# SCH-Unified_Sheet_1_Altium.net
KiCad netlist of a schematic drawn in Altium Designer
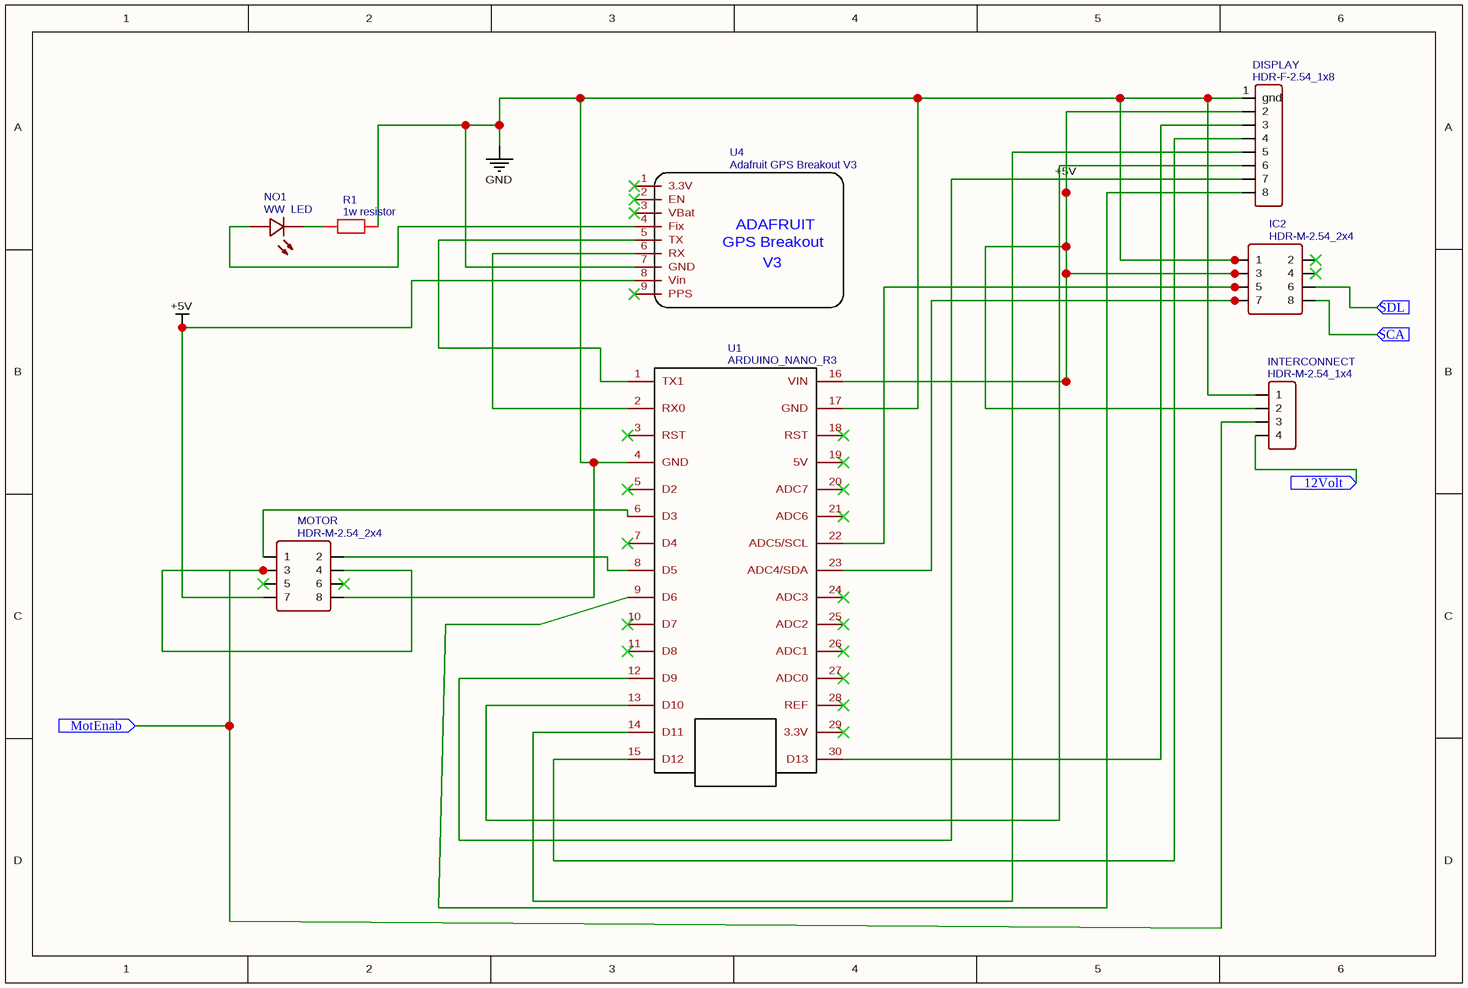
[diagram p0: SCH-Unified_Sheet_1_Altium.schdoc]

(export (version "E")
  (design (tool "Eeschema 10.0.6"))
  (components
    (comp (ref "DISPLAY")
      (value "HDR-F-2.54_1x8")
      (fields (field (name "CONTRIBUTOR") "LCEDA_Lib"))
      (libsource (lib "altium-import") (part "root_0_HDR-F-2.54_1x8_"))
    )
    (comp (ref "IC2")
      (value "HDR-M-2.54_2x4")
      (fields (field (name "CONTRIBUTOR") "LCEDA_Lib"))
      (libsource (lib "altium-import") (part "root_0_HDR-M-2.54_2x4_"))
    )
    (comp (ref "INTERCONNECT")
      (value "HDR-M-2.54_1x4")
      (fields (field (name "CONTRIBUTOR") "LCEDA_Lib"))
      (libsource (lib "altium-import") (part "root_0_HDR-M-2.54_1x4_"))
    )
    (comp (ref "MOTOR")
      (value "HDR-M-2.54_2x4")
      (fields (field (name "CONTRIBUTOR") "LCEDA_Lib"))
      (libsource (lib "altium-import") (part "root_0_HDR-M-2.54_2x4_"))
    )
    (comp (ref "NO1")
      (value "WW  LED")
      (fields (field (name "MANUFACTURER PART") "LED-3mm红") (field (name "CONTRIBUTOR") "csnagyt"))
      (libsource (lib "altium-import") (part "root_2_WW  LED_"))
    )
    (comp (ref "R1")
      (value "1w resistor")
      (fields (field (name "CONTRIBUTOR") "Kagutsuchi"))
      (libsource (lib "altium-import") (part "root_0_1w resistor_"))
    )
    (comp (ref "U1")
      (value "ARDUINO_NANO_R3")
      (fields (field (name "CONTRIBUTOR") "Nikolay Yanev"))
      (libsource (lib "altium-import") (part "root_0_ARDUINO_NANO_R3_"))
    )
    (comp (ref "U4")
      (value "Adafruit GPS Breakout V3")
      (fields (field (name "MANUFACTURER PART") "New SchematicLib") (field (name "CONTRIBUTOR") "NiklasC"))
      (libsource (lib "altium-import") (part "root_0_Adafruit GPS Breakout V3_"))
    )
  )
  (nets
    (net (code "1") (name "+5V") (class "Default")
      (node (ref "DISPLAY") (pin "2") (pinfunction "2_2") (pintype "passive"))
      (node (ref "IC2") (pin "3") (pinfunction "3_3") (pintype "passive"))
      (node (ref "INTERCONNECT") (pin "2") (pinfunction "2_2") (pintype "passive"))
      (node (ref "MOTOR") (pin "7") (pinfunction "7_7") (pintype "passive"))
      (node (ref "U1") (pin "16") (pinfunction "VIN_16") (pintype "passive"))
      (node (ref "U4") (pin "8") (pinfunction "Vin_8") (pintype "passive"))
    )
    (net (code "2") (name "/12Volt") (class "Default")
      (node (ref "INTERCONNECT") (pin "4") (pinfunction "4_4") (pintype "passive"))
    )
    (net (code "3") (name "/MotEnab") (class "Default")
      (node (ref "INTERCONNECT") (pin "3") (pinfunction "3_3") (pintype "passive"))
      (node (ref "MOTOR") (pin "3") (pinfunction "3_3") (pintype "passive"))
      (node (ref "MOTOR") (pin "4") (pinfunction "4_4") (pintype "passive"))
    )
    (net (code "4") (name "/SCA") (class "Default")
      (node (ref "IC2") (pin "8") (pinfunction "8_8") (pintype "passive"))
    )
    (net (code "5") (name "/SDL") (class "Default")
      (node (ref "IC2") (pin "6") (pinfunction "6_6") (pintype "passive"))
    )
    (net (code "6") (name "GND") (class "Default")
      (node (ref "DISPLAY") (pin "1") (pinfunction "gnd_1") (pintype "passive"))
      (node (ref "IC2") (pin "1") (pinfunction "1_1") (pintype "passive"))
      (node (ref "INTERCONNECT") (pin "1") (pinfunction "1_1") (pintype "passive"))
      (node (ref "MOTOR") (pin "8") (pinfunction "8_8") (pintype "passive"))
      (node (ref "R1") (pin "2") (pinfunction "1_2") (pintype "passive"))
      (node (ref "U1") (pin "17") (pinfunction "GND_17") (pintype "passive"))
      (node (ref "U1") (pin "4") (pinfunction "GND_4") (pintype "passive"))
      (node (ref "U4") (pin "7") (pinfunction "GND_7") (pintype "passive"))
    )
    (net (code "7") (name "Net-(R1-2)") (class "Default")
      (node (ref "NO1") (pin "2") (pinfunction "2_2") (pintype "passive"))
      (node (ref "R1") (pin "1") (pinfunction "2_1") (pintype "passive"))
    )
    (net (code "8") (name "Net-(U1-ADC4{slash}SDA)") (class "Default")
      (node (ref "IC2") (pin "7") (pinfunction "7_7") (pintype "passive"))
      (node (ref "U1") (pin "23") (pinfunction "ADC4/SDA_23") (pintype "passive"))
    )
    (net (code "9") (name "Net-(U1-ADC5{slash}SCL)") (class "Default")
      (node (ref "IC2") (pin "5") (pinfunction "5_5") (pintype "passive"))
      (node (ref "U1") (pin "22") (pinfunction "ADC5/SCL_22") (pintype "passive"))
    )
    (net (code "10") (name "Net-(U1-D3)") (class "Default")
      (node (ref "MOTOR") (pin "1") (pinfunction "1_1") (pintype "passive"))
      (node (ref "U1") (pin "6") (pinfunction "D3_6") (pintype "passive"))
    )
    (net (code "11") (name "Net-(U1-D5)") (class "Default")
      (node (ref "MOTOR") (pin "2") (pinfunction "2_2") (pintype "passive"))
      (node (ref "U1") (pin "8") (pinfunction "D5_8") (pintype "passive"))
    )
    (net (code "12") (name "Net-(U1-D6)") (class "Default")
      (node (ref "DISPLAY") (pin "8") (pinfunction "8_8") (pintype "passive"))
      (node (ref "U1") (pin "9") (pinfunction "D6_9") (pintype "passive"))
    )
    (net (code "13") (name "Net-(U1-D9)") (class "Default")
      (node (ref "DISPLAY") (pin "7") (pinfunction "7_7") (pintype "passive"))
      (node (ref "U1") (pin "12") (pinfunction "D9_12") (pintype "passive"))
    )
    (net (code "14") (name "Net-(U1-D10)") (class "Default")
      (node (ref "DISPLAY") (pin "6") (pinfunction "6_6") (pintype "passive"))
      (node (ref "U1") (pin "13") (pinfunction "D10_13") (pintype "passive"))
    )
    (net (code "15") (name "Net-(U1-D11)") (class "Default")
      (node (ref "DISPLAY") (pin "5") (pinfunction "5_5") (pintype "passive"))
      (node (ref "U1") (pin "14") (pinfunction "D11_14") (pintype "passive"))
    )
    (net (code "16") (name "Net-(U1-D12)") (class "Default")
      (node (ref "DISPLAY") (pin "4") (pinfunction "4_4") (pintype "passive"))
      (node (ref "U1") (pin "15") (pinfunction "D12_15") (pintype "passive"))
    )
    (net (code "17") (name "Net-(U1-D13)") (class "Default")
      (node (ref "DISPLAY") (pin "3") (pinfunction "3_3") (pintype "passive"))
      (node (ref "U1") (pin "30") (pinfunction "D13_30") (pintype "passive"))
    )
    (net (code "18") (name "Net-(U1-RX0)") (class "Default")
      (node (ref "U1") (pin "2") (pinfunction "RX0_2") (pintype "passive"))
      (node (ref "U4") (pin "6") (pinfunction "RX_6") (pintype "passive"))
    )
    (net (code "19") (name "Net-(U1-TX1)") (class "Default")
      (node (ref "U1") (pin "1") (pinfunction "TX1_1") (pintype "passive"))
      (node (ref "U4") (pin "5") (pinfunction "TX_5") (pintype "passive"))
    )
    (net (code "20") (name "Net-(U4-Fix)") (class "Default")
      (node (ref "NO1") (pin "1") (pinfunction "1_1") (pintype "passive"))
      (node (ref "U4") (pin "4") (pinfunction "Fix_4") (pintype "passive"))
    )
    (net (code "21") (name "unconnected-(IC2-Pad2)") (class "Default")
      (node (ref "IC2") (pin "2") (pinfunction "2_2") (pintype "passive+no_connect"))
    )
    (net (code "22") (name "unconnected-(IC2-Pad4)") (class "Default")
      (node (ref "IC2") (pin "4") (pinfunction "4_4") (pintype "passive+no_connect"))
    )
    (net (code "23") (name "unconnected-(MOTOR-Pad5)") (class "Default")
      (node (ref "MOTOR") (pin "5") (pinfunction "5_5") (pintype "passive+no_connect"))
    )
    (net (code "24") (name "unconnected-(MOTOR-Pad6)") (class "Default")
      (node (ref "MOTOR") (pin "6") (pinfunction "6_6") (pintype "passive+no_connect"))
    )
    (net (code "25") (name "unconnected-(U1-3.3V-Pad29)") (class "Default")
      (node (ref "U1") (pin "29") (pinfunction "3.3V_29") (pintype "passive+no_connect"))
    )
    (net (code "26") (name "unconnected-(U1-5V-Pad19)") (class "Default")
      (node (ref "U1") (pin "19") (pinfunction "5V_19") (pintype "passive+no_connect"))
    )
    (net (code "27") (name "unconnected-(U1-ADC0-Pad27)") (class "Default")
      (node (ref "U1") (pin "27") (pinfunction "ADC0_27") (pintype "passive+no_connect"))
    )
    (net (code "28") (name "unconnected-(U1-ADC1-Pad26)") (class "Default")
      (node (ref "U1") (pin "26") (pinfunction "ADC1_26") (pintype "passive+no_connect"))
    )
    (net (code "29") (name "unconnected-(U1-ADC2-Pad25)") (class "Default")
      (node (ref "U1") (pin "25") (pinfunction "ADC2_25") (pintype "passive+no_connect"))
    )
    (net (code "30") (name "unconnected-(U1-ADC3-Pad24)") (class "Default")
      (node (ref "U1") (pin "24") (pinfunction "ADC3_24") (pintype "passive+no_connect"))
    )
    (net (code "31") (name "unconnected-(U1-ADC6-Pad21)") (class "Default")
      (node (ref "U1") (pin "21") (pinfunction "ADC6_21") (pintype "passive+no_connect"))
    )
    (net (code "32") (name "unconnected-(U1-ADC7-Pad20)") (class "Default")
      (node (ref "U1") (pin "20") (pinfunction "ADC7_20") (pintype "passive+no_connect"))
    )
    (net (code "33") (name "unconnected-(U1-D2-Pad5)") (class "Default")
      (node (ref "U1") (pin "5") (pinfunction "D2_5") (pintype "passive+no_connect"))
    )
    (net (code "34") (name "unconnected-(U1-D4-Pad7)") (class "Default")
      (node (ref "U1") (pin "7") (pinfunction "D4_7") (pintype "passive+no_connect"))
    )
    (net (code "35") (name "unconnected-(U1-D7-Pad10)") (class "Default")
      (node (ref "U1") (pin "10") (pinfunction "D7_10") (pintype "passive+no_connect"))
    )
    (net (code "36") (name "unconnected-(U1-D8-Pad11)") (class "Default")
      (node (ref "U1") (pin "11") (pinfunction "D8_11") (pintype "passive+no_connect"))
    )
    (net (code "37") (name "unconnected-(U1-REF-Pad28)") (class "Default")
      (node (ref "U1") (pin "28") (pinfunction "REF_28") (pintype "passive+no_connect"))
    )
    (net (code "38") (name "unconnected-(U1-RST-Pad3)") (class "Default")
      (node (ref "U1") (pin "3") (pinfunction "RST_3") (pintype "passive+no_connect"))
    )
    (net (code "39") (name "unconnected-(U1-RST-Pad18)") (class "Default")
      (node (ref "U1") (pin "18") (pinfunction "RST_18") (pintype "passive+no_connect"))
    )
    (net (code "40") (name "unconnected-(U4-3.3V-Pad1)") (class "Default")
      (node (ref "U4") (pin "1") (pinfunction "3.3V_1") (pintype "passive+no_connect"))
    )
    (net (code "41") (name "unconnected-(U4-EN-Pad2)") (class "Default")
      (node (ref "U4") (pin "2") (pinfunction "EN_2") (pintype "passive+no_connect"))
    )
    (net (code "42") (name "unconnected-(U4-PPS-Pad9)") (class "Default")
      (node (ref "U4") (pin "9") (pinfunction "PPS_9") (pintype "passive+no_connect"))
    )
    (net (code "43") (name "unconnected-(U4-VBat-Pad3)") (class "Default")
      (node (ref "U4") (pin "3") (pinfunction "VBat_3") (pintype "passive+no_connect"))
    )
  )
)
